# Main_Modular_Board_V1_0.net
KiCad netlist of a schematic drawn in EAGLE
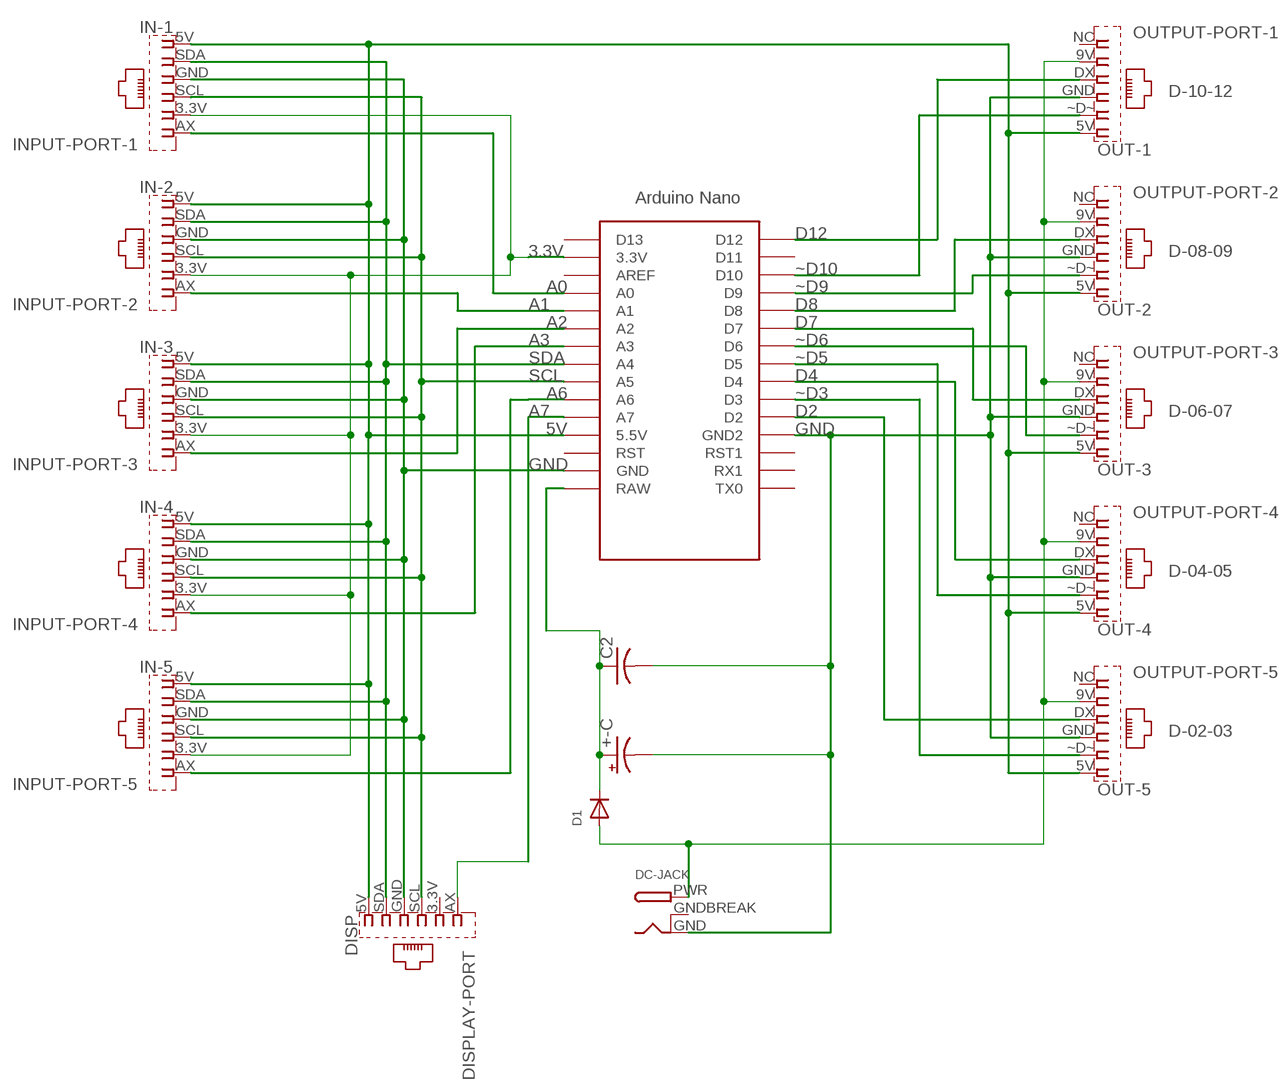
[diagram p0: schematic, sheet 1]

(export (version "E")
  (design (tool "Eeschema 10.0.6"))
  (components
    (comp (ref "+-C")
      (value "CPOL-USE2.5-6")
      (footprint "eagle-import:E2,5-6")
      (libsource (lib "eagle-import") (part "CPOL-USE2.5-6"))
    )
    (comp (ref "C2")
      (value "C-US025-025X050")
      (footprint "eagle-import:C025-025X050")
      (libsource (lib "eagle-import") (part "C-US025-025X050"))
    )
    (comp (ref "D1")
      (value "DIODEDO-1N4148")
      (footprint "eagle-import:DO-1N4148")
      (libsource (lib "eagle-import") (part "DIODEDO-1N4148"))
    )
    (comp (ref "DC-JACK")
      (value "DCBARRELPTH")
      (footprint "eagle-import:DCJACK_2MM_PTH")
      (libsource (lib "eagle-import") (part "DCBARRELPTH"))
    )
    (comp (ref "DISP")
      (value "DISPLAY-PORT")
      (footprint "eagle-import:ELEMENTORY-IN-BRD")
      (libsource (lib "eagle-import") (part "ELEMENTORY-RJ11INPUT-BOARD"))
    )
    (comp (ref "IN-1")
      (value "INPUT-PORT-1")
      (footprint "eagle-import:ELEMENTORY-IN-BRD")
      (libsource (lib "eagle-import") (part "ELEMENTORY-RJ11INPUT-BOARD"))
    )
    (comp (ref "IN-2")
      (value "INPUT-PORT-2")
      (footprint "eagle-import:ELEMENTORY-IN-BRD")
      (libsource (lib "eagle-import") (part "ELEMENTORY-RJ11INPUT-BOARD"))
    )
    (comp (ref "IN-3")
      (value "INPUT-PORT-3")
      (footprint "eagle-import:ELEMENTORY-IN-BRD")
      (libsource (lib "eagle-import") (part "ELEMENTORY-RJ11INPUT-BOARD"))
    )
    (comp (ref "IN-4")
      (value "INPUT-PORT-4")
      (footprint "eagle-import:ELEMENTORY-IN-BRD")
      (libsource (lib "eagle-import") (part "ELEMENTORY-RJ11INPUT-BOARD"))
    )
    (comp (ref "IN-5")
      (value "INPUT-PORT-5")
      (footprint "eagle-import:ELEMENTORY-IN-BRD")
      (libsource (lib "eagle-import") (part "ELEMENTORY-RJ11INPUT-BOARD"))
    )
    (comp (ref "OUT-1")
      (value "OUTPUT-PORT-1")
      (footprint "eagle-import:ELEMENTORY-OUT-BRD")
      (libsource (lib "eagle-import") (part "ELEMENTORY-RJ11OUTPUT-BOARD"))
    )
    (comp (ref "OUT-2")
      (value "OUTPUT-PORT-2")
      (footprint "eagle-import:ELEMENTORY-OUT-BRD")
      (libsource (lib "eagle-import") (part "ELEMENTORY-RJ11OUTPUT-BOARD"))
    )
    (comp (ref "OUT-3")
      (value "OUTPUT-PORT-3")
      (footprint "eagle-import:ELEMENTORY-OUT-BRD")
      (libsource (lib "eagle-import") (part "ELEMENTORY-RJ11OUTPUT-BOARD"))
    )
    (comp (ref "OUT-4")
      (value "OUTPUT-PORT-4")
      (footprint "eagle-import:ELEMENTORY-OUT-BRD")
      (libsource (lib "eagle-import") (part "ELEMENTORY-RJ11OUTPUT-BOARD"))
    )
    (comp (ref "OUT-5")
      (value "OUTPUT-PORT-5")
      (footprint "eagle-import:ELEMENTORY-OUT-BRD")
      (libsource (lib "eagle-import") (part "ELEMENTORY-RJ11OUTPUT-BOARD"))
    )
    (comp (ref "U$1")
      (value "NANO")
      (footprint "eagle-import:NANO")
      (libsource (lib "eagle-import") (part "NANO"))
    )
  )
  (nets
    (net (code "1") (name "/3.3V") (class "Default")
      (node (ref "IN-1") (pin "3.3V") (pinfunction "5_3.3V") (pintype "passive"))
      (node (ref "IN-2") (pin "3.3V") (pinfunction "5_3.3V") (pintype "passive"))
      (node (ref "IN-3") (pin "3.3V") (pinfunction "5_3.3V") (pintype "passive"))
      (node (ref "IN-4") (pin "3.3V") (pinfunction "5_3.3V") (pintype "passive"))
      (node (ref "IN-5") (pin "3.3V") (pinfunction "5_3.3V") (pintype "passive"))
      (node (ref "U$1") (pin "3.3V") (pinfunction "3.3V_3.3V") (pintype "bidirectional"))
    )
    (net (code "2") (name "/5V") (class "Default")
      (node (ref "DISP") (pin "5V") (pinfunction "1_5V") (pintype "passive"))
      (node (ref "IN-1") (pin "5V") (pinfunction "1_5V") (pintype "passive"))
      (node (ref "IN-2") (pin "5V") (pinfunction "1_5V") (pintype "passive"))
      (node (ref "IN-3") (pin "5V") (pinfunction "1_5V") (pintype "passive"))
      (node (ref "IN-4") (pin "5V") (pinfunction "1_5V") (pintype "passive"))
      (node (ref "IN-5") (pin "5V") (pinfunction "1_5V") (pintype "passive"))
      (node (ref "OUT-1") (pin "5V") (pinfunction "1_5V") (pintype "passive"))
      (node (ref "OUT-2") (pin "5V") (pinfunction "1_5V") (pintype "passive"))
      (node (ref "OUT-3") (pin "5V") (pinfunction "1_5V") (pintype "passive"))
      (node (ref "OUT-4") (pin "5V") (pinfunction "1_5V") (pintype "passive"))
      (node (ref "OUT-5") (pin "5V") (pinfunction "1_5V") (pintype "passive"))
      (node (ref "U$1") (pin "5V") (pinfunction "5.5V_5V") (pintype "bidirectional"))
    )
    (net (code "3") (name "/A0") (class "Default")
      (node (ref "IN-1") (pin "AX") (pinfunction "6_AX") (pintype "passive"))
      (node (ref "U$1") (pin "A0") (pinfunction "A0_A0") (pintype "bidirectional"))
    )
    (net (code "4") (name "/A1") (class "Default")
      (node (ref "IN-2") (pin "AX") (pinfunction "6_AX") (pintype "passive"))
      (node (ref "U$1") (pin "A1") (pinfunction "A1_A1") (pintype "bidirectional"))
    )
    (net (code "5") (name "/A2") (class "Default")
      (node (ref "IN-3") (pin "AX") (pinfunction "6_AX") (pintype "passive"))
      (node (ref "U$1") (pin "A2") (pinfunction "A2_A2") (pintype "bidirectional"))
    )
    (net (code "6") (name "/A3") (class "Default")
      (node (ref "IN-4") (pin "AX") (pinfunction "6_AX") (pintype "passive"))
      (node (ref "U$1") (pin "A3") (pinfunction "A3_A3") (pintype "bidirectional"))
    )
    (net (code "7") (name "/A6") (class "Default")
      (node (ref "IN-5") (pin "AX") (pinfunction "6_AX") (pintype "passive"))
      (node (ref "U$1") (pin "A6") (pinfunction "A6_A6") (pintype "bidirectional"))
    )
    (net (code "8") (name "/A7") (class "Default")
      (node (ref "DISP") (pin "AX") (pinfunction "6_AX") (pintype "passive"))
      (node (ref "U$1") (pin "A7") (pinfunction "A7_A7") (pintype "bidirectional"))
    )
    (net (code "9") (name "/D2") (class "Default")
      (node (ref "OUT-5") (pin "DX") (pinfunction "4_DX") (pintype "passive"))
      (node (ref "U$1") (pin "D2") (pinfunction "D2_D2") (pintype "bidirectional"))
    )
    (net (code "10") (name "/D4") (class "Default")
      (node (ref "OUT-4") (pin "DX") (pinfunction "4_DX") (pintype "passive"))
      (node (ref "U$1") (pin "D4") (pinfunction "D4_D4") (pintype "bidirectional"))
    )
    (net (code "11") (name "/D7") (class "Default")
      (node (ref "OUT-3") (pin "DX") (pinfunction "4_DX") (pintype "passive"))
      (node (ref "U$1") (pin "D7") (pinfunction "D7_D7") (pintype "bidirectional"))
    )
    (net (code "12") (name "/D8") (class "Default")
      (node (ref "OUT-2") (pin "DX") (pinfunction "4_DX") (pintype "passive"))
      (node (ref "U$1") (pin "D8") (pinfunction "D8_D8") (pintype "bidirectional"))
    )
    (net (code "13") (name "/D12") (class "Default")
      (node (ref "OUT-1") (pin "DX") (pinfunction "4_DX") (pintype "passive"))
      (node (ref "U$1") (pin "D12") (pinfunction "D12_D12") (pintype "bidirectional"))
    )
    (net (code "14") (name "/GND") (class "Default")
      (node (ref "+-C") (pin "-") (pinfunction "-_-") (pintype "passive"))
      (node (ref "C2") (pin "2") (pinfunction "2_2") (pintype "passive"))
      (node (ref "DC-JACK") (pin "GND") (pinfunction "GND_GND") (pintype "power_in"))
      (node (ref "DISP") (pin "GND") (pinfunction "3_GND") (pintype "passive"))
      (node (ref "IN-1") (pin "GND") (pinfunction "3_GND") (pintype "passive"))
      (node (ref "IN-2") (pin "GND") (pinfunction "3_GND") (pintype "passive"))
      (node (ref "IN-3") (pin "GND") (pinfunction "3_GND") (pintype "passive"))
      (node (ref "IN-4") (pin "GND") (pinfunction "3_GND") (pintype "passive"))
      (node (ref "IN-5") (pin "GND") (pinfunction "3_GND") (pintype "passive"))
      (node (ref "OUT-1") (pin "GND") (pinfunction "3_GND") (pintype "passive"))
      (node (ref "OUT-2") (pin "GND") (pinfunction "3_GND") (pintype "passive"))
      (node (ref "OUT-3") (pin "GND") (pinfunction "3_GND") (pintype "passive"))
      (node (ref "OUT-4") (pin "GND") (pinfunction "3_GND") (pintype "passive"))
      (node (ref "OUT-5") (pin "GND") (pinfunction "3_GND") (pintype "passive"))
      (node (ref "U$1") (pin "GND") (pinfunction "GND_GND") (pintype "bidirectional"))
      (node (ref "U$1") (pin "GND1") (pinfunction "GND2_GND1") (pintype "bidirectional"))
    )
    (net (code "15") (name "/GNDBREAK") (class "Default")
      (node (ref "DC-JACK") (pin "GNDBREAK") (pinfunction "GNDBREAK_GNDBREAK") (pintype "power_in"))
    )
    (net (code "16") (name "/SCL") (class "Default")
      (node (ref "DISP") (pin "SCL") (pinfunction "4_SCL") (pintype "passive"))
      (node (ref "IN-1") (pin "SCL") (pinfunction "4_SCL") (pintype "passive"))
      (node (ref "IN-2") (pin "SCL") (pinfunction "4_SCL") (pintype "passive"))
      (node (ref "IN-3") (pin "SCL") (pinfunction "4_SCL") (pintype "passive"))
      (node (ref "IN-4") (pin "SCL") (pinfunction "4_SCL") (pintype "passive"))
      (node (ref "IN-5") (pin "SCL") (pinfunction "4_SCL") (pintype "passive"))
      (node (ref "U$1") (pin "A5") (pinfunction "A5_A5") (pintype "bidirectional"))
    )
    (net (code "17") (name "/SDA") (class "Default")
      (node (ref "DISP") (pin "SDA") (pinfunction "2_SDA") (pintype "passive"))
      (node (ref "IN-1") (pin "SDA") (pinfunction "2_SDA") (pintype "passive"))
      (node (ref "IN-2") (pin "SDA") (pinfunction "2_SDA") (pintype "passive"))
      (node (ref "IN-3") (pin "SDA") (pinfunction "2_SDA") (pintype "passive"))
      (node (ref "IN-4") (pin "SDA") (pinfunction "2_SDA") (pintype "passive"))
      (node (ref "IN-5") (pin "SDA") (pinfunction "2_SDA") (pintype "passive"))
      (node (ref "U$1") (pin "A4") (pinfunction "A4_A4") (pintype "bidirectional"))
    )
    (net (code "18") (name "/~{D3}") (class "Default")
      (node (ref "OUT-5") (pin "~D~") (pinfunction "2_~D~") (pintype "passive"))
      (node (ref "U$1") (pin "D3") (pinfunction "D3_D3") (pintype "bidirectional"))
    )
    (net (code "19") (name "/~{D5}") (class "Default")
      (node (ref "OUT-4") (pin "~D~") (pinfunction "2_~D~") (pintype "passive"))
      (node (ref "U$1") (pin "D5") (pinfunction "D5_D5") (pintype "bidirectional"))
    )
    (net (code "20") (name "/~{D6}") (class "Default")
      (node (ref "OUT-3") (pin "~D~") (pinfunction "2_~D~") (pintype "passive"))
      (node (ref "U$1") (pin "D6") (pinfunction "D6_D6") (pintype "bidirectional"))
    )
    (net (code "21") (name "/~{D9}") (class "Default")
      (node (ref "OUT-2") (pin "~D~") (pinfunction "2_~D~") (pintype "passive"))
      (node (ref "U$1") (pin "D9") (pinfunction "D9_D9") (pintype "bidirectional"))
    )
    (net (code "22") (name "/~{D10}") (class "Default")
      (node (ref "OUT-1") (pin "~D~") (pinfunction "2_~D~") (pintype "passive"))
      (node (ref "U$1") (pin "D10") (pinfunction "D10_D10") (pintype "bidirectional"))
    )
    (net (code "23") (name "Net-(+-C-Pad+)") (class "Default")
      (node (ref "+-C") (pin "+") (pinfunction "+_+") (pintype "passive"))
      (node (ref "C2") (pin "1") (pinfunction "1_1") (pintype "passive"))
      (node (ref "D1") (pin "C") (pinfunction "C_C") (pintype "passive"))
      (node (ref "U$1") (pin "RAW") (pinfunction "RAW_RAW") (pintype "bidirectional"))
    )
    (net (code "24") (name "Net-(OUT-1-5)") (class "Default")
      (node (ref "D1") (pin "A") (pinfunction "A_A") (pintype "passive"))
      (node (ref "DC-JACK") (pin "PWR") (pinfunction "PWR_PWR") (pintype "power_in"))
      (node (ref "OUT-1") (pin "9V") (pinfunction "5_9V") (pintype "passive"))
      (node (ref "OUT-2") (pin "9V") (pinfunction "5_9V") (pintype "passive"))
      (node (ref "OUT-3") (pin "9V") (pinfunction "5_9V") (pintype "passive"))
      (node (ref "OUT-4") (pin "9V") (pinfunction "5_9V") (pintype "passive"))
      (node (ref "OUT-5") (pin "9V") (pinfunction "5_9V") (pintype "passive"))
    )
    (net (code "25") (name "unconnected-(DISP-5-Pad3.3V)") (class "Default")
      (node (ref "DISP") (pin "3.3V") (pinfunction "5_3.3V") (pintype "passive"))
    )
    (net (code "26") (name "unconnected-(OUT-1-6-PadNC)") (class "Default")
      (node (ref "OUT-1") (pin "NC") (pinfunction "6_NC") (pintype "passive"))
    )
    (net (code "27") (name "unconnected-(OUT-2-6-PadNC)") (class "Default")
      (node (ref "OUT-2") (pin "NC") (pinfunction "6_NC") (pintype "passive"))
    )
    (net (code "28") (name "unconnected-(OUT-3-6-PadNC)") (class "Default")
      (node (ref "OUT-3") (pin "NC") (pinfunction "6_NC") (pintype "passive"))
    )
    (net (code "29") (name "unconnected-(OUT-4-6-PadNC)") (class "Default")
      (node (ref "OUT-4") (pin "NC") (pinfunction "6_NC") (pintype "passive"))
    )
    (net (code "30") (name "unconnected-(OUT-5-6-PadNC)") (class "Default")
      (node (ref "OUT-5") (pin "NC") (pinfunction "6_NC") (pintype "passive"))
    )
    (net (code "31") (name "unconnected-(U$1-PadAREF)") (class "Default")
      (node (ref "U$1") (pin "AREF") (pinfunction "AREF_AREF") (pintype "bidirectional"))
    )
    (net (code "32") (name "unconnected-(U$1-PadD11)") (class "Default")
      (node (ref "U$1") (pin "D11") (pinfunction "D11_D11") (pintype "bidirectional"))
    )
    (net (code "33") (name "unconnected-(U$1-PadD13)") (class "Default")
      (node (ref "U$1") (pin "D13") (pinfunction "D13_D13") (pintype "bidirectional"))
    )
    (net (code "34") (name "unconnected-(U$1-PadICSP1)") (class "Default")
      (node (ref "U$1") (pin "ICSP1") (pinfunction "ICSP1_ICSP1") (pintype "bidirectional"))
    )
    (net (code "35") (name "unconnected-(U$1-PadICSP2)") (class "Default")
      (node (ref "U$1") (pin "ICSP2") (pinfunction "ICSP2_ICSP2") (pintype "bidirectional"))
    )
    (net (code "36") (name "unconnected-(U$1-PadICSP3)") (class "Default")
      (node (ref "U$1") (pin "ICSP3") (pinfunction "ICSP3_ICSP3") (pintype "bidirectional"))
    )
    (net (code "37") (name "unconnected-(U$1-PadICSP4)") (class "Default")
      (node (ref "U$1") (pin "ICSP4") (pinfunction "ICSP4_ICSP4") (pintype "bidirectional"))
    )
    (net (code "38") (name "unconnected-(U$1-PadICSP5)") (class "Default")
      (node (ref "U$1") (pin "ICSP5") (pinfunction "ICSP5_ICSP5") (pintype "bidirectional"))
    )
    (net (code "39") (name "unconnected-(U$1-PadICSP6)") (class "Default")
      (node (ref "U$1") (pin "ICSP6") (pinfunction "ICSP6_ICSP6") (pintype "bidirectional"))
    )
    (net (code "40") (name "unconnected-(U$1-PadRST)") (class "Default")
      (node (ref "U$1") (pin "RST") (pinfunction "RST_RST") (pintype "bidirectional"))
    )
    (net (code "41") (name "unconnected-(U$1-PadRST1)") (class "Default")
      (node (ref "U$1") (pin "RST1") (pinfunction "RST1_RST1") (pintype "bidirectional"))
    )
    (net (code "42") (name "unconnected-(U$1-PadRX1)") (class "Default")
      (node (ref "U$1") (pin "RX1") (pinfunction "RX1_RX1") (pintype "bidirectional"))
    )
    (net (code "43") (name "unconnected-(U$1-PadTX0)") (class "Default")
      (node (ref "U$1") (pin "TX0") (pinfunction "TX0_TX0") (pintype "bidirectional"))
    )
  )
)
